# Sturing_Bout.net
KiCad netlist of a schematic drawn in Altium Designer
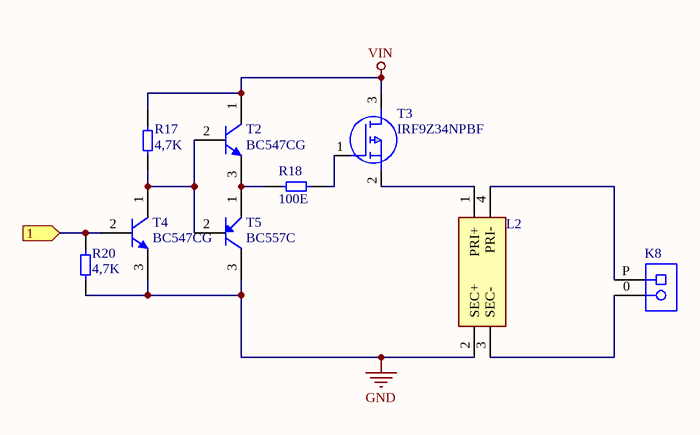
[diagram p0: Sturing_Bout.SchDoc]

(export (version "E")
  (design (tool "Eeschema 10.0.6"))
  (components
    (comp (ref "K8")
      (value "1729128")
      (footprint "PHOE-1729128-2_V")
      (description "PCB Terminal Block, 13.5 A, 400 V, 2-Pin THD, RoHS, Bulk")
      (fields (field (name "MANUFACTURER") "Phoenix Contact"))
      (libsource (lib "Soldeerstation") (part "CMP-2000-05815-1"))
    )
    (comp (ref "L2")
      (value "~")
      (footprint "CM2545X171B10")
      (description "Common Mode Chokes Dual 170Ohm 100MHz 10A 0.01Ohm DCR Thru-Hole Bulk")
      (fields (field (name "MANUFACTURER_PART_NUMBER") "CM2545X171B-10"))
      (libsource (lib "Soldeerstation") (part "CM2545X171B-10_1"))
    )
    (comp (ref "R17")
      (value "4,7K")
      (footprint "RESC2013X60X40ML20T25")
      (fields (field (name "PART NUMBER") "ERA6AEB332V") (field (name "MANUFACTURER") "Panasonic"))
      (libsource (lib "Soldeerstation") (part "CMP-2001-00629-1_1"))
    )
    (comp (ref "R18")
      (value "100E")
      (footprint "RESC2013X60X40ML20T25")
      (fields (field (name "PART NUMBER") "ERA6AEB332V") (field (name "MANUFACTURER") "Panasonic"))
      (libsource (lib "Soldeerstation") (part "CMP-2001-00629-1_1"))
    )
    (comp (ref "R20")
      (value "4,7K")
      (footprint "RESC2013X60X40ML20T25")
      (fields (field (name "PART NUMBER") "ERA6AEB332V") (field (name "MANUFACTURER") "Panasonic"))
      (libsource (lib "Soldeerstation") (part "CMP-2001-00629-1_1"))
    )
    (comp (ref "T2")
      (value "BC547CG")
      (footprint "ONSC-TO-92-3-29-11")
      (description "Amplifier Transistor, NPN Silicon, 3-Pin TO-92, Pb-Free, Bulk Box")
      (fields (field (name "MANUFACTURER") "On Semiconductor"))
      (libsource (lib "Soldeerstation") (part "CMP-1048-01464-1"))
    )
    (comp (ref "T3")
      (value "IRF9Z34NPBF")
      (footprint "TO254P469X1042X1967-3P")
      (description "MOSFET MOSFT PCh -55V -17A 100mOhm 23.3nC")
      (fields (field (name "MOUSER PART NUMBER") "942-IRF9Z34NPBF"))
      (libsource (lib "Soldeerstation") (part "IRF9Z34NPBF"))
    )
    (comp (ref "T4")
      (value "BC547CG")
      (footprint "ONSC-TO-92-3-29-11")
      (description "Amplifier Transistor, NPN Silicon, 3-Pin TO-92, Pb-Free, Bulk Box")
      (fields (field (name "MANUFACTURER") "On Semiconductor"))
      (libsource (lib "Soldeerstation") (part "CMP-1048-01464-1"))
    )
    (comp (ref "T5")
      (value "BC557C")
      (footprint "ONSC-TO-92-3-29-11")
      (description "Amplifier Transistor, PNP Silicon, 3-Pin TO-92, Bulk Box")
      (fields (field (name "MANUFACTURER") "On Semiconductor"))
      (libsource (lib "Soldeerstation") (part "CMP-1048-01449-1"))
    )
  )
  (nets
    (net (code "1") (name "/1") (class "Default")
      (node (ref "R20") (pin "1") (pinfunction "1_1") (pintype "passive"))
      (node (ref "T4") (pin "2") (pinfunction "B_2") (pintype "passive"))
    )
    (net (code "2") (name "GND") (class "Default")
      (node (ref "L2") (pin "2") (pinfunction "SEC+_2") (pintype "passive"))
      (node (ref "R20") (pin "2") (pinfunction "2_2") (pintype "passive"))
      (node (ref "T4") (pin "3") (pinfunction "E_3") (pintype "passive"))
      (node (ref "T5") (pin "3") (pinfunction "E_3") (pintype "passive"))
    )
    (net (code "3") (name "Net-(K8-1)") (class "Default")
      (node (ref "K8") (pin "P") (pinfunction "1_P") (pintype "passive"))
      (node (ref "L2") (pin "4") (pinfunction "PRI-_4") (pintype "passive"))
    )
    (net (code "4") (name "Net-(K8-2)") (class "Default")
      (node (ref "K8") (pin "0") (pinfunction "2_0") (pintype "passive"))
      (node (ref "L2") (pin "3") (pinfunction "SEC-_3") (pintype "passive"))
    )
    (net (code "5") (name "Net-(L2-PRI+)") (class "Default")
      (node (ref "L2") (pin "1") (pinfunction "PRI+_1") (pintype "passive"))
      (node (ref "T3") (pin "2") (pinfunction "S_2") (pintype "passive"))
    )
    (net (code "6") (name "Net-(T2-B)") (class "Default")
      (node (ref "R17") (pin "2") (pinfunction "2_2") (pintype "passive"))
      (node (ref "T2") (pin "2") (pinfunction "B_2") (pintype "passive"))
      (node (ref "T4") (pin "1") (pinfunction "C_1") (pintype "passive"))
      (node (ref "T5") (pin "2") (pinfunction "B_2") (pintype "passive"))
    )
    (net (code "7") (name "Net-(T2-E)") (class "Default")
      (node (ref "R18") (pin "1") (pinfunction "1_1") (pintype "passive"))
      (node (ref "T2") (pin "3") (pinfunction "E_3") (pintype "passive"))
      (node (ref "T5") (pin "1") (pinfunction "C_1") (pintype "passive"))
    )
    (net (code "8") (name "Net-(T3-G)") (class "Default")
      (node (ref "R18") (pin "2") (pinfunction "2_2") (pintype "passive"))
      (node (ref "T3") (pin "1") (pinfunction "G_1") (pintype "passive"))
    )
    (net (code "9") (name "VIN") (class "Default")
      (node (ref "R17") (pin "1") (pinfunction "1_1") (pintype "passive"))
      (node (ref "T2") (pin "1") (pinfunction "C_1") (pintype "passive"))
      (node (ref "T3") (pin "3") (pinfunction "D_3") (pintype "passive"))
    )
  )
)
